# MCU.net
KiCad netlist of a schematic drawn in Altium Designer
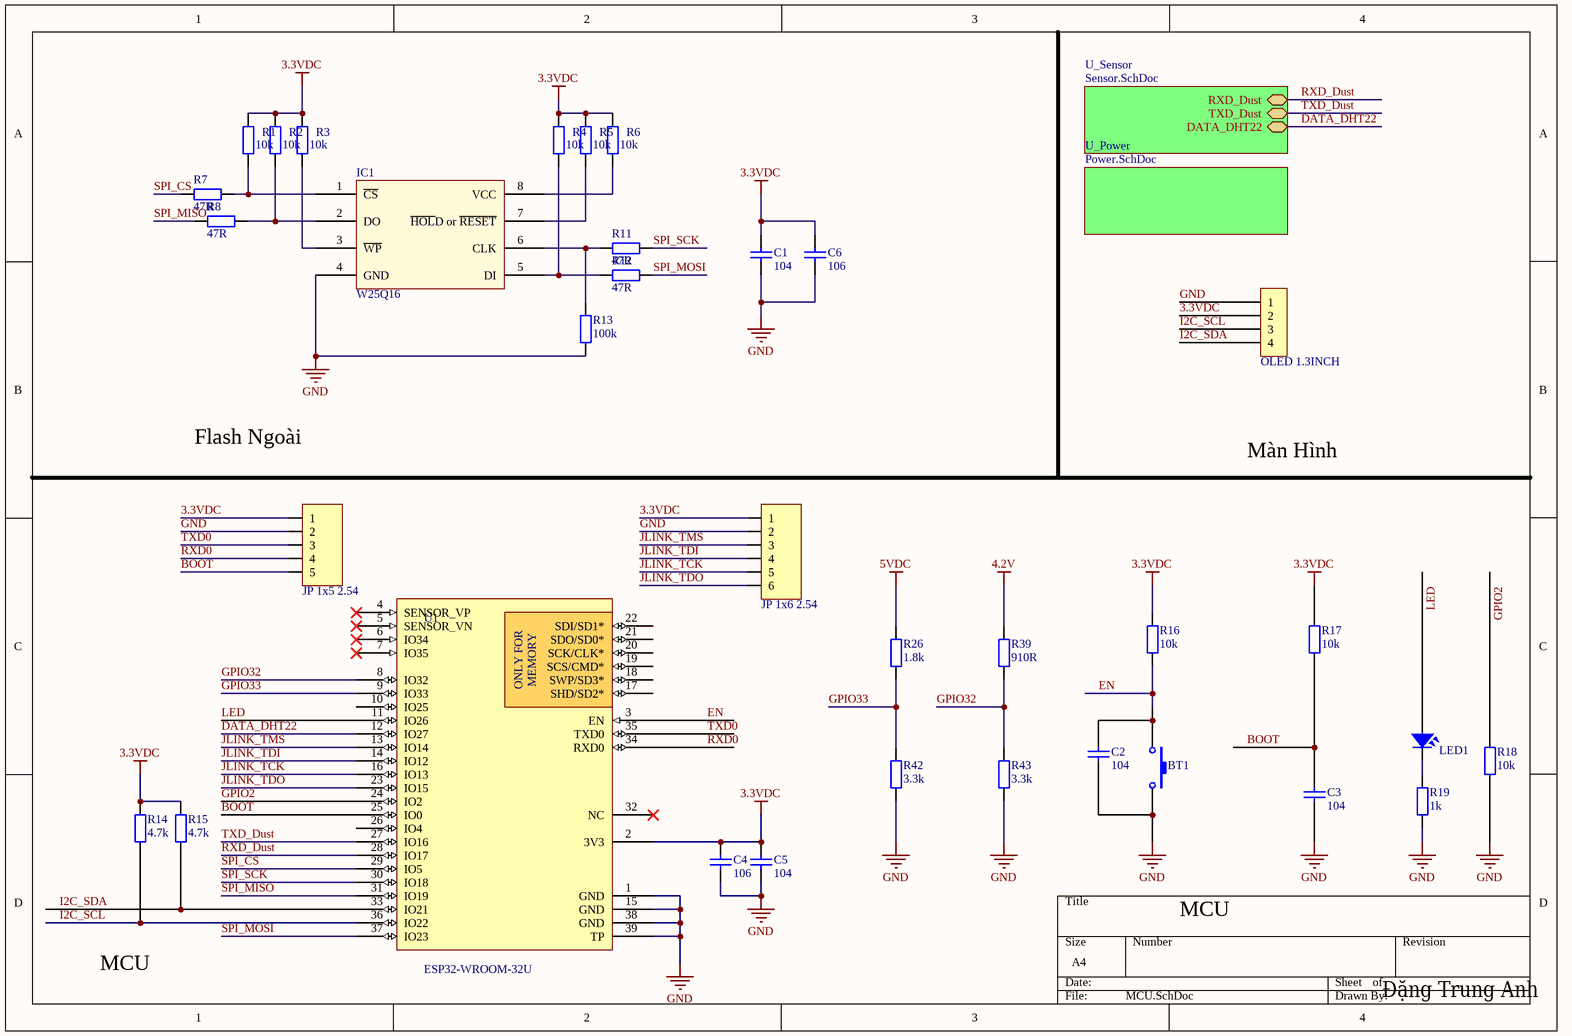
[diagram p0: MCU.SchDoc]

(export (version "E")
  (design (tool "Eeschema 10.0.6"))
  (components
    (comp (ref "BT1")
      (value "Nut Nhan 2 Chan SMD 3x6x2.5")
      (footprint "Nut Nhan 2 Chan SMD 3x6x2.5")
      (libsource (lib "Altium_Lib_by_KhueNguyenCreator") (part "Nut Nhan 2 Chan SMD 3x6x2.5"))
    )
    (comp (ref "C1")
      (value "104")
      (footprint "Tu 0805")
      (description "Dán")
      (libsource (lib "THU VIEN SCH") (part "Tu 104"))
    )
    (comp (ref "C2")
      (value "104")
      (footprint "tu 0805")
      (description "Dán")
      (libsource (lib "Altium_Lib_by_KhueNguyenCreator") (part "Tu 0805 104 50V 10%"))
    )
    (comp (ref "C3")
      (value "104")
      (footprint "tu 0805")
      (description "Dán")
      (libsource (lib "Altium_Lib_by_KhueNguyenCreator") (part "Tu 0805 104 50V 10%"))
    )
    (comp (ref "C4")
      (value "106")
      (footprint "Tu 0805")
      (description "Dán")
      (libsource (lib "THU VIEN SCH") (part "Tu 0805 106 16V 10%"))
    )
    (comp (ref "C5")
      (value "104")
      (footprint "tu 0805")
      (description "Dán")
      (libsource (lib "THU VIEN SCH") (part "Tu 0805 104 50V 10%"))
    )
    (comp (ref "C6")
      (value "106")
      (footprint "Tu 0805")
      (description "Dán")
      (libsource (lib "THU VIEN SCH") (part "Tu 0805 106 16V 10%"))
    )
    (comp (ref "IC1")
      (value "W25Q16")
      (footprint "W25Q16 -SOIC8")
      (libsource (lib "Integrated_Library") (part "W25Q16"))
    )
    (comp (ref "JP1")
      (value "OLED 1.3INCH")
      (footprint "JP 1x4 CT - OLED")
      (description "Cắm")
      (libsource (lib "Altium_Lib_by_KhueNguyenCreator") (part "JP 1x4 2.54 Cai Thang"))
    )
    (comp (ref "JP2")
      (value "JP 1x5 2.54")
      (footprint "JP 1x5 DT")
      (description "Cắm")
      (libsource (lib "Altium_Lib_by_KhueNguyenCreator") (part "JP 1x5 2.54 Duc Thang"))
    )
    (comp (ref "JP3")
      (value "JP 1x6 2.54")
      (footprint "JP 1x6 DT")
      (description "Cắm")
      (libsource (lib "Altium_Lib_by_KhueNguyenCreator") (part "JP 1x6 2.54 Duc Thang"))
    )
    (comp (ref "LED1")
      (value "LED SMD")
      (footprint "SM-LED-0805-Blue")
      (libsource (lib "syhaunguyen") (part "LED-SMD-0805"))
    )
    (comp (ref "R1")
      (value "10k")
      (footprint "tro smd 0805")
      (description "Dán")
      (libsource (lib "THU VIEN SCH") (part "Tro 0805 5% 10k"))
    )
    (comp (ref "R2")
      (value "10k")
      (footprint "tro smd 0805")
      (description "Dán")
      (libsource (lib "THU VIEN SCH") (part "Tro 0805 5% 10k"))
    )
    (comp (ref "R3")
      (value "10k")
      (footprint "tro smd 0805")
      (description "Dán")
      (libsource (lib "THU VIEN SCH") (part "Tro 0805 5% 10k"))
    )
    (comp (ref "R4")
      (value "10k")
      (footprint "tro smd 0805")
      (description "Dán")
      (libsource (lib "THU VIEN SCH") (part "Tro 0805 5% 10k"))
    )
    (comp (ref "R5")
      (value "10k")
      (footprint "tro smd 0805")
      (description "Dán")
      (libsource (lib "THU VIEN SCH") (part "Tro 0805 5% 10k"))
    )
    (comp (ref "R6")
      (value "10k")
      (footprint "tro smd 0805")
      (description "Dán")
      (libsource (lib "THU VIEN SCH") (part "Tro 0805 5% 10k"))
    )
    (comp (ref "R7")
      (value "47R")
      (footprint "tro smd 0805")
      (description "Dán")
      (libsource (lib "THU VIEN SCH") (part "Tro 0805 5% 47R"))
    )
    (comp (ref "R8")
      (value "47R")
      (footprint "tro smd 0805")
      (description "Dán")
      (libsource (lib "THU VIEN SCH") (part "Tro 0805 5% 47R"))
    )
    (comp (ref "R11")
      (value "47R")
      (footprint "tro smd 0805")
      (description "Dán")
      (libsource (lib "THU VIEN SCH") (part "Tro 0805 5% 47R"))
    )
    (comp (ref "R12")
      (value "47R")
      (footprint "tro smd 0805")
      (description "Dán")
      (libsource (lib "THU VIEN SCH") (part "Tro 0805 5% 47R"))
    )
    (comp (ref "R13")
      (value "100k")
      (footprint "tro smd 0805")
      (description "Dán")
      (libsource (lib "THU VIEN SCH") (part "Tro 0805 5% 100k"))
    )
    (comp (ref "R14")
      (value "4.7k")
      (footprint "tro smd 0805")
      (description "Dán")
      (libsource (lib "THU VIEN SCH") (part "Tro 0805 1% 10k"))
    )
    (comp (ref "R15")
      (value "4.7k")
      (footprint "tro smd 0805")
      (description "Dán")
      (libsource (lib "THU VIEN SCH") (part "Tro 0805 1% 10k"))
    )
    (comp (ref "R16")
      (value "10k")
      (footprint "tro smd 0805")
      (description "Dán")
      (libsource (lib "Altium_Lib_by_KhueNguyenCreator") (part "Tro 0805 5% 12k"))
    )
    (comp (ref "R17")
      (value "10k")
      (footprint "tro smd 0805")
      (description "Dán")
      (libsource (lib "Altium_Lib_by_KhueNguyenCreator") (part "Tro 0805 5% 12k"))
    )
    (comp (ref "R18")
      (value "10k")
      (footprint "tro smd 0805")
      (description "Dán")
      (libsource (lib "Altium_Lib_by_KhueNguyenCreator") (part "Tro 0805 5% 12k"))
    )
    (comp (ref "R19")
      (value "1k")
      (footprint "tro smd 0805")
      (description "Dán")
      (libsource (lib "THU VIEN SCH") (part "Tro 0805 5% 100R"))
    )
    (comp (ref "R26")
      (value "1.8k")
      (footprint "tro smd 0805")
      (description "Dán")
      (libsource (lib "Altium_Lib_by_KhueNguyenCreator") (part "Tro 0805 1% 1.8k"))
    )
    (comp (ref "R39")
      (value "910R")
      (footprint "tro smd 0805")
      (description "Dán")
      (libsource (lib "Altium_Lib_by_KhueNguyenCreator") (part "Tro 0805 1% 910R"))
    )
    (comp (ref "R42")
      (value "3.3k")
      (footprint "tro smd 0805")
      (description "Dán")
      (libsource (lib "Altium_Lib_by_KhueNguyenCreator") (part "Tro 0805 1% 3.3k"))
    )
    (comp (ref "R43")
      (value "3.3k")
      (footprint "tro smd 0805")
      (description "Dán")
      (libsource (lib "Altium_Lib_by_KhueNguyenCreator") (part "Tro 0805 1% 3.3k"))
    )
    (comp (ref "U1")
      (value "ESP32-WROOM-32U")
      (footprint "ESP32-WROOM-32")
      (description "Wi-Fi/BT BLE Module ESP32-D0WD")
      (fields (field (name "MFR") "Espressif"))
      (libsource (lib "BYTECH_HW_LIB_2019 (1)") (part "ESP32-WROOM-32U"))
    )
  )
  (nets
    (net (code "1") (name "/BOOT") (class "Default")
      (node (ref "C3") (pin "1") (pinfunction "1_1") (pintype "passive"))
      (node (ref "JP2") (pin "5") (pinfunction "5_5") (pintype "passive"))
      (node (ref "R17") (pin "1") (pinfunction "1_1") (pintype "passive"))
      (node (ref "U1") (pin "25") (pinfunction "IO0_25") (pintype "bidirectional"))
    )
    (net (code "2") (name "/DATA_DHT22") (class "Default")
      (node (ref "U1") (pin "12") (pinfunction "IO27_12") (pintype "bidirectional"))
    )
    (net (code "3") (name "/EN") (class "Default")
      (node (ref "BT1") (pin "1") (pinfunction "1_1") (pintype "passive"))
      (node (ref "C2") (pin "1") (pinfunction "1_1") (pintype "passive"))
      (node (ref "R16") (pin "1") (pinfunction "1_1") (pintype "passive"))
      (node (ref "U1") (pin "3") (pinfunction "EN_3") (pintype "input"))
    )
    (net (code "4") (name "/GPIO2") (class "Default")
      (node (ref "R18") (pin "2") (pinfunction "2_2") (pintype "passive"))
      (node (ref "U1") (pin "24") (pinfunction "IO2_24") (pintype "bidirectional"))
    )
    (net (code "5") (name "/GPIO32") (class "Default")
      (node (ref "R39") (pin "1") (pinfunction "1_1") (pintype "passive"))
      (node (ref "R43") (pin "2") (pinfunction "2_2") (pintype "passive"))
      (node (ref "U1") (pin "8") (pinfunction "IO32_8") (pintype "bidirectional"))
    )
    (net (code "6") (name "/GPIO33") (class "Default")
      (node (ref "R26") (pin "1") (pinfunction "1_1") (pintype "passive"))
      (node (ref "R42") (pin "2") (pinfunction "2_2") (pintype "passive"))
      (node (ref "U1") (pin "9") (pinfunction "IO33_9") (pintype "bidirectional"))
    )
    (net (code "7") (name "/I2C_SCL") (class "Default")
      (node (ref "JP1") (pin "3") (pinfunction "3_3") (pintype "passive"))
      (node (ref "R14") (pin "1") (pinfunction "1_1") (pintype "passive"))
      (node (ref "U1") (pin "36") (pinfunction "IO22_36") (pintype "bidirectional"))
    )
    (net (code "8") (name "/I2C_SDA") (class "Default")
      (node (ref "JP1") (pin "4") (pinfunction "4_4") (pintype "passive"))
      (node (ref "R15") (pin "1") (pinfunction "1_1") (pintype "passive"))
      (node (ref "U1") (pin "33") (pinfunction "IO21_33") (pintype "bidirectional"))
    )
    (net (code "9") (name "/JLINK_TCK") (class "Default")
      (node (ref "JP3") (pin "5") (pinfunction "5_5") (pintype "passive"))
      (node (ref "U1") (pin "16") (pinfunction "IO13_16") (pintype "bidirectional"))
    )
    (net (code "10") (name "/JLINK_TDI") (class "Default")
      (node (ref "JP3") (pin "4") (pinfunction "4_4") (pintype "passive"))
      (node (ref "U1") (pin "14") (pinfunction "IO12_14") (pintype "bidirectional"))
    )
    (net (code "11") (name "/JLINK_TDO") (class "Default")
      (node (ref "JP3") (pin "6") (pinfunction "6_6") (pintype "passive"))
      (node (ref "U1") (pin "23") (pinfunction "IO15_23") (pintype "bidirectional"))
    )
    (net (code "12") (name "/JLINK_TMS") (class "Default")
      (node (ref "JP3") (pin "3") (pinfunction "3_3") (pintype "passive"))
      (node (ref "U1") (pin "13") (pinfunction "IO14_13") (pintype "bidirectional"))
    )
    (net (code "13") (name "/LED") (class "Default")
      (node (ref "LED1") (pin "1") (pinfunction "1_1") (pintype "passive"))
      (node (ref "U1") (pin "11") (pinfunction "IO26_11") (pintype "bidirectional"))
    )
    (net (code "14") (name "/RXD0") (class "Default")
      (node (ref "JP2") (pin "4") (pinfunction "4_4") (pintype "passive"))
      (node (ref "U1") (pin "34") (pinfunction "RXD0_34") (pintype "bidirectional"))
    )
    (net (code "15") (name "/RXD_Dust") (class "Default")
      (node (ref "U1") (pin "28") (pinfunction "IO17_28") (pintype "bidirectional"))
    )
    (net (code "16") (name "/SPI_CS") (class "Default")
      (node (ref "R7") (pin "1") (pinfunction "1_1") (pintype "passive"))
      (node (ref "U1") (pin "29") (pinfunction "IO5_29") (pintype "bidirectional"))
    )
    (net (code "17") (name "/SPI_MISO") (class "Default")
      (node (ref "R8") (pin "1") (pinfunction "1_1") (pintype "passive"))
      (node (ref "U1") (pin "31") (pinfunction "IO19_31") (pintype "bidirectional"))
    )
    (net (code "18") (name "/SPI_MOSI") (class "Default")
      (node (ref "R12") (pin "2") (pinfunction "2_2") (pintype "passive"))
      (node (ref "U1") (pin "37") (pinfunction "IO23_37") (pintype "bidirectional"))
    )
    (net (code "19") (name "/SPI_SCK") (class "Default")
      (node (ref "R11") (pin "2") (pinfunction "2_2") (pintype "passive"))
      (node (ref "U1") (pin "30") (pinfunction "IO18_30") (pintype "bidirectional"))
    )
    (net (code "20") (name "/TXD0") (class "Default")
      (node (ref "JP2") (pin "3") (pinfunction "3_3") (pintype "passive"))
      (node (ref "U1") (pin "35") (pinfunction "TXD0_35") (pintype "bidirectional"))
    )
    (net (code "21") (name "/TXD_Dust") (class "Default")
      (node (ref "U1") (pin "27") (pinfunction "IO16_27") (pintype "bidirectional"))
    )
    (net (code "22") (name "3.3VDC") (class "Default")
      (node (ref "C1") (pin "2") (pinfunction "2_2") (pintype "passive"))
      (node (ref "C4") (pin "1") (pinfunction "1_1") (pintype "passive"))
      (node (ref "C5") (pin "1") (pinfunction "1_1") (pintype "passive"))
      (node (ref "C6") (pin "2") (pinfunction "2_2") (pintype "passive"))
      (node (ref "JP1") (pin "2") (pinfunction "2_2") (pintype "passive"))
      (node (ref "JP2") (pin "1") (pinfunction "1_1") (pintype "passive"))
      (node (ref "JP3") (pin "1") (pinfunction "1_1") (pintype "passive"))
      (node (ref "R1") (pin "2") (pinfunction "2_2") (pintype "passive"))
      (node (ref "R14") (pin "2") (pinfunction "2_2") (pintype "passive"))
      (node (ref "R15") (pin "2") (pinfunction "2_2") (pintype "passive"))
      (node (ref "R16") (pin "2") (pinfunction "2_2") (pintype "passive"))
      (node (ref "R17") (pin "2") (pinfunction "2_2") (pintype "passive"))
      (node (ref "R2") (pin "2") (pinfunction "2_2") (pintype "passive"))
      (node (ref "R3") (pin "2") (pinfunction "2_2") (pintype "passive"))
      (node (ref "R4") (pin "2") (pinfunction "2_2") (pintype "passive"))
      (node (ref "R5") (pin "2") (pinfunction "2_2") (pintype "passive"))
      (node (ref "R6") (pin "2") (pinfunction "2_2") (pintype "passive"))
      (node (ref "U1") (pin "2") (pinfunction "3V3_2") (pintype "power_in"))
    )
    (net (code "23") (name "4.2V") (class "Default")
      (node (ref "R39") (pin "2") (pinfunction "2_2") (pintype "passive"))
    )
    (net (code "24") (name "5VDC") (class "Default")
      (node (ref "R26") (pin "2") (pinfunction "2_2") (pintype "passive"))
    )
    (net (code "25") (name "GND") (class "Default")
      (node (ref "BT1") (pin "2") (pinfunction "2_2") (pintype "passive"))
      (node (ref "C1") (pin "1") (pinfunction "1_1") (pintype "passive"))
      (node (ref "C2") (pin "2") (pinfunction "2_2") (pintype "passive"))
      (node (ref "C3") (pin "2") (pinfunction "2_2") (pintype "passive"))
      (node (ref "C4") (pin "2") (pinfunction "2_2") (pintype "passive"))
      (node (ref "C5") (pin "2") (pinfunction "2_2") (pintype "passive"))
      (node (ref "C6") (pin "1") (pinfunction "1_1") (pintype "passive"))
      (node (ref "IC1") (pin "4") (pinfunction "GND_4") (pintype "passive"))
      (node (ref "JP1") (pin "1") (pinfunction "1_1") (pintype "passive"))
      (node (ref "JP2") (pin "2") (pinfunction "2_2") (pintype "passive"))
      (node (ref "JP3") (pin "2") (pinfunction "2_2") (pintype "passive"))
      (node (ref "R13") (pin "1") (pinfunction "1_1") (pintype "passive"))
      (node (ref "R18") (pin "1") (pinfunction "1_1") (pintype "passive"))
      (node (ref "R19") (pin "1") (pinfunction "1_1") (pintype "passive"))
      (node (ref "R42") (pin "1") (pinfunction "1_1") (pintype "passive"))
      (node (ref "R43") (pin "1") (pinfunction "1_1") (pintype "passive"))
      (node (ref "U1") (pin "1") (pinfunction "GND_1") (pintype "power_in"))
      (node (ref "U1") (pin "15") (pinfunction "GND_15") (pintype "power_in"))
      (node (ref "U1") (pin "38") (pinfunction "GND_38") (pintype "power_in"))
      (node (ref "U1") (pin "39") (pinfunction "TP_39") (pintype "power_in"))
    )
    (net (code "26") (name "Net-(IC1-CLK)") (class "Default")
      (node (ref "IC1") (pin "6") (pinfunction "CLK_6") (pintype "passive"))
      (node (ref "R11") (pin "1") (pinfunction "1_1") (pintype "passive"))
      (node (ref "R13") (pin "2") (pinfunction "2_2") (pintype "passive"))
    )
    (net (code "27") (name "Net-(IC1-DI)") (class "Default")
      (node (ref "IC1") (pin "5") (pinfunction "DI_5") (pintype "passive"))
      (node (ref "R12") (pin "1") (pinfunction "1_1") (pintype "passive"))
      (node (ref "R4") (pin "1") (pinfunction "1_1") (pintype "passive"))
    )
    (net (code "28") (name "Net-(IC1-DO)") (class "Default")
      (node (ref "IC1") (pin "2") (pinfunction "DO_2") (pintype "passive"))
      (node (ref "R2") (pin "1") (pinfunction "1_1") (pintype "passive"))
      (node (ref "R8") (pin "2") (pinfunction "2_2") (pintype "passive"))
    )
    (net (code "29") (name "Net-(IC1-VCC)") (class "Default")
      (node (ref "IC1") (pin "8") (pinfunction "VCC_8") (pintype "passive"))
      (node (ref "R6") (pin "1") (pinfunction "1_1") (pintype "passive"))
    )
    (net (code "30") (name "Net-(IC1-~{CS})") (class "Default")
      (node (ref "IC1") (pin "1") (pinfunction "~{CS}_1") (pintype "passive"))
      (node (ref "R1") (pin "1") (pinfunction "1_1") (pintype "passive"))
      (node (ref "R7") (pin "2") (pinfunction "2_2") (pintype "passive"))
    )
    (net (code "31") (name "Net-(IC1-~{HOL}D_or_~{RESET})") (class "Default")
      (node (ref "IC1") (pin "7") (pinfunction "~{HOL}D_or_~{RESET}_7") (pintype "passive"))
      (node (ref "R5") (pin "1") (pinfunction "1_1") (pintype "passive"))
    )
    (net (code "32") (name "Net-(IC1-~{WP})") (class "Default")
      (node (ref "IC1") (pin "3") (pinfunction "~{WP}_3") (pintype "passive"))
      (node (ref "R3") (pin "1") (pinfunction "1_1") (pintype "passive"))
    )
    (net (code "33") (name "Net-(LED1-Pad2)") (class "Default")
      (node (ref "LED1") (pin "2") (pinfunction "2_2") (pintype "passive"))
      (node (ref "R19") (pin "2") (pinfunction "2_2") (pintype "passive"))
    )
    (net (code "34") (name "unconnected-(U1-IO4-Pad26)") (class "Default")
      (node (ref "U1") (pin "26") (pinfunction "IO4_26") (pintype "bidirectional"))
    )
    (net (code "35") (name "unconnected-(U1-IO25-Pad10)") (class "Default")
      (node (ref "U1") (pin "10") (pinfunction "IO25_10") (pintype "bidirectional"))
    )
    (net (code "36") (name "unconnected-(U1-IO34-Pad6)") (class "Default")
      (node (ref "U1") (pin "6") (pinfunction "IO34_6") (pintype "input+no_connect"))
    )
    (net (code "37") (name "unconnected-(U1-IO35-Pad7)") (class "Default")
      (node (ref "U1") (pin "7") (pinfunction "IO35_7") (pintype "input+no_connect"))
    )
    (net (code "38") (name "unconnected-(U1-NC-Pad32)") (class "Default")
      (node (ref "U1") (pin "32") (pinfunction "NC_32") (pintype "passive+no_connect"))
    )
    (net (code "39") (name "unconnected-(U1-SCK{slash}CLK*-Pad20)") (class "Default")
      (node (ref "U1") (pin "20") (pinfunction "SCK/CLK*_20") (pintype "bidirectional"))
    )
    (net (code "40") (name "unconnected-(U1-SCS{slash}CMD*-Pad19)") (class "Default")
      (node (ref "U1") (pin "19") (pinfunction "SCS/CMD*_19") (pintype "bidirectional"))
    )
    (net (code "41") (name "unconnected-(U1-SDI{slash}SD1*-Pad22)") (class "Default")
      (node (ref "U1") (pin "22") (pinfunction "SDI/SD1*_22") (pintype "bidirectional"))
    )
    (net (code "42") (name "unconnected-(U1-SDO{slash}SD0*-Pad21)") (class "Default")
      (node (ref "U1") (pin "21") (pinfunction "SDO/SD0*_21") (pintype "bidirectional"))
    )
    (net (code "43") (name "unconnected-(U1-SENSOR_VN-Pad5)") (class "Default")
      (node (ref "U1") (pin "5") (pinfunction "SENSOR_VN_5") (pintype "input+no_connect"))
    )
    (net (code "44") (name "unconnected-(U1-SENSOR_VP-Pad4)") (class "Default")
      (node (ref "U1") (pin "4") (pinfunction "SENSOR_VP_4") (pintype "input+no_connect"))
    )
    (net (code "45") (name "unconnected-(U1-SHD{slash}SD2*-Pad17)") (class "Default")
      (node (ref "U1") (pin "17") (pinfunction "SHD/SD2*_17") (pintype "bidirectional"))
    )
    (net (code "46") (name "unconnected-(U1-SWP{slash}SD3*-Pad18)") (class "Default")
      (node (ref "U1") (pin "18") (pinfunction "SWP/SD3*_18") (pintype "bidirectional"))
    )
  )
)
